# Sumo_Motor_Stepper_DC.net
KiCad netlist of a schematic drawn in Altium Designer
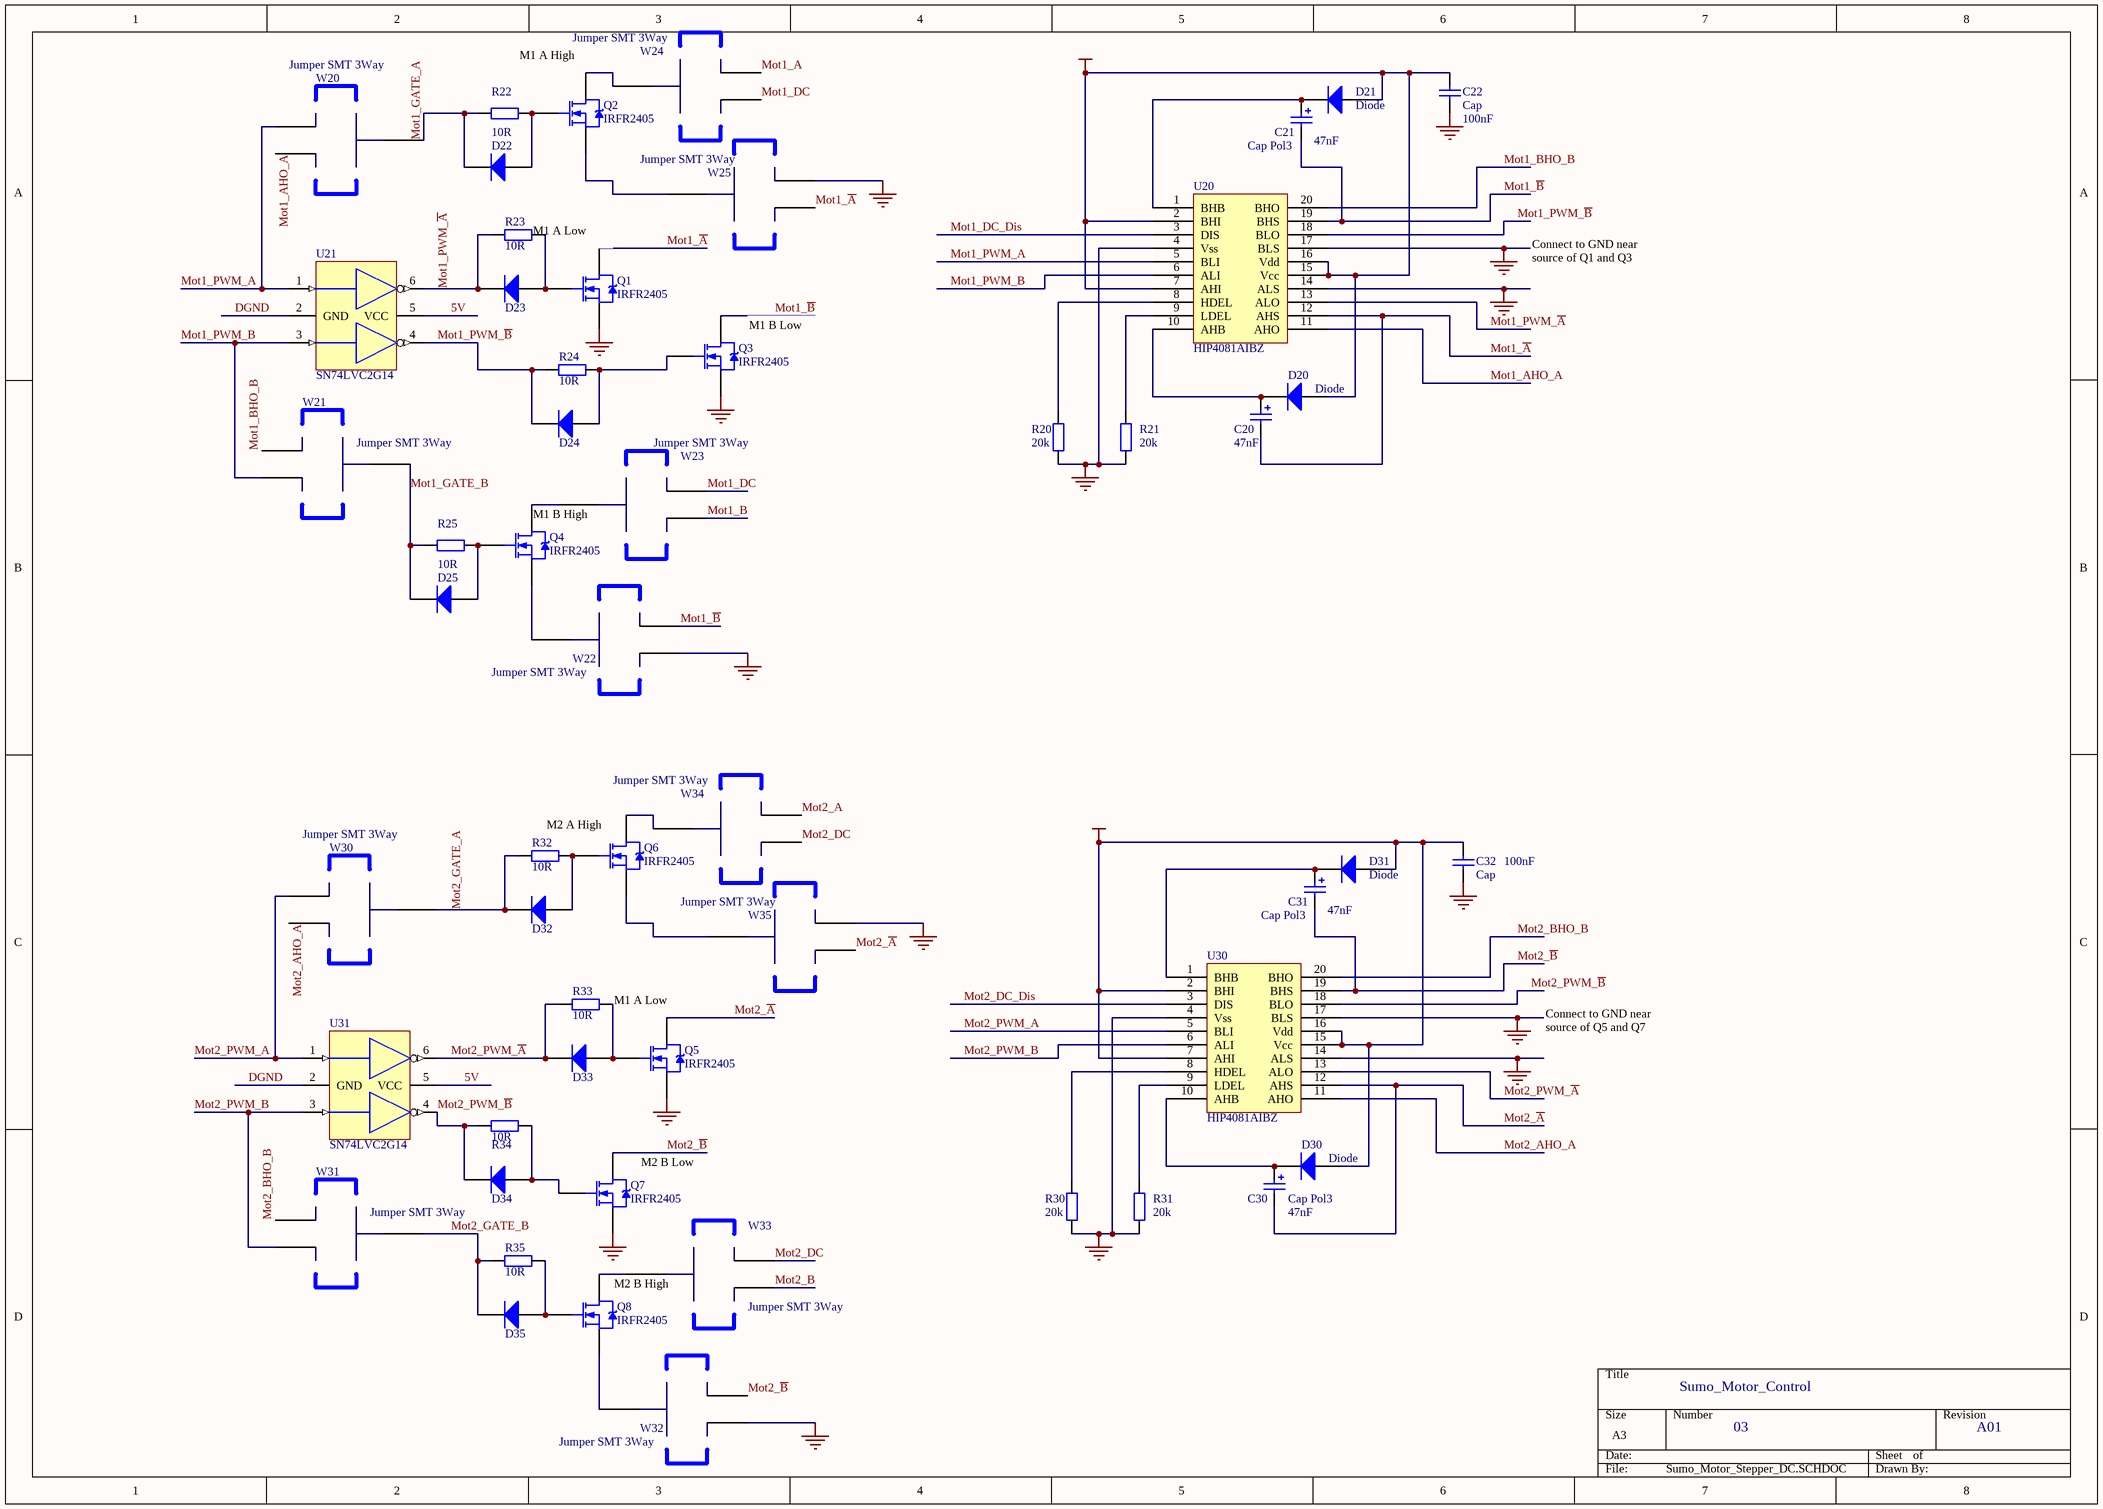
[diagram p0: Sumo_Motor_Stepper_DC.SCHDOC]

(export (version "E")
  (design (tool "Eeschema 10.0.6"))
  (components
    (comp (ref "C20")
      (value "47nF")
      (footprint "CC2012-0805")
      (description "Polarized Capacitor (Surface Mount)")
      (fields (field (name "Comment") "Cap Pol3") (field (name "PUBLISHER") "Altium Limited"))
      (libsource (lib "*") (part "Cap Pol3"))
    )
    (comp (ref "C21")
      (value "Cap Pol3")
      (footprint "CC2012-0805")
      (description "Polarized Capacitor (Surface Mount)")
      (fields (field (name "ALTIUM_VALUE") "47nF") (field (name "PUBLISHER") "Altium Limited"))
      (libsource (lib "*") (part "Cap Pol3"))
    )
    (comp (ref "C22")
      (value "Cap")
      (footprint "CC2012-0805")
      (description "Capacitor")
      (fields (field (name "ALTIUM_VALUE") "100nF") (field (name "PUBLISHER") "Altium Limited"))
      (libsource (lib "*") (part "Cap"))
    )
    (comp (ref "C30")
      (value "Cap Pol3")
      (footprint "CC2012-0805")
      (description "Polarized Capacitor (Surface Mount)")
      (fields (field (name "ALTIUM_VALUE") "47nF") (field (name "PUBLISHER") "Altium Limited"))
      (libsource (lib "*") (part "Cap Pol3"))
    )
    (comp (ref "C31")
      (value "Cap Pol3")
      (footprint "CC2012-0805")
      (description "Polarized Capacitor (Surface Mount)")
      (fields (field (name "ALTIUM_VALUE") "47nF") (field (name "PUBLISHER") "Altium Limited"))
      (libsource (lib "*") (part "Cap Pol3"))
    )
    (comp (ref "C32")
      (value "Cap")
      (footprint "CC2012-0805")
      (description "Capacitor")
      (fields (field (name "ALTIUM_VALUE") "100nF") (field (name "PUBLISHER") "Altium Limited"))
      (libsource (lib "*") (part "Cap"))
    )
    (comp (ref "D20")
      (value "Diode")
      (footprint "SMA")
      (description "Default Diode")
      (fields (field (name "PUBLISHER") "Altium Limited"))
      (libsource (lib "*") (part "Diode"))
    )
    (comp (ref "D21")
      (value "Diode")
      (footprint "SMA")
      (description "Default Diode")
      (fields (field (name "PUBLISHER") "Altium Limited"))
      (libsource (lib "*") (part "Diode"))
    )
    (comp (ref "D22")
      (value "Diode")
      (footprint "SMA")
      (description "Default Diode")
      (fields (field (name "PUBLISHER") "Altium Limited"))
      (libsource (lib "*") (part "Diode"))
    )
    (comp (ref "D23")
      (value "Diode")
      (footprint "SMA")
      (description "Default Diode")
      (fields (field (name "PUBLISHER") "Altium Limited"))
      (libsource (lib "*") (part "Diode"))
    )
    (comp (ref "D24")
      (value "Diode")
      (footprint "SMA")
      (description "Default Diode")
      (fields (field (name "PUBLISHER") "Altium Limited"))
      (libsource (lib "*") (part "Diode"))
    )
    (comp (ref "D25")
      (value "Diode")
      (footprint "SMA")
      (description "Default Diode")
      (fields (field (name "PUBLISHER") "Altium Limited"))
      (libsource (lib "*") (part "Diode"))
    )
    (comp (ref "D30")
      (value "Diode")
      (footprint "SMA")
      (description "Default Diode")
      (fields (field (name "PUBLISHER") "Altium Limited"))
      (libsource (lib "*") (part "Diode"))
    )
    (comp (ref "D31")
      (value "Diode")
      (footprint "SMA")
      (description "Default Diode")
      (fields (field (name "PUBLISHER") "Altium Limited"))
      (libsource (lib "*") (part "Diode"))
    )
    (comp (ref "D32")
      (value "Diode")
      (footprint "SMA")
      (description "Default Diode")
      (fields (field (name "PUBLISHER") "Altium Limited"))
      (libsource (lib "*") (part "Diode"))
    )
    (comp (ref "D33")
      (value "Diode")
      (footprint "SMA")
      (description "Default Diode")
      (fields (field (name "PUBLISHER") "Altium Limited"))
      (libsource (lib "*") (part "Diode"))
    )
    (comp (ref "D34")
      (value "Diode")
      (footprint "SMA")
      (description "Default Diode")
      (fields (field (name "PUBLISHER") "Altium Limited"))
      (libsource (lib "*") (part "Diode"))
    )
    (comp (ref "D35")
      (value "Diode")
      (footprint "SMA")
      (description "Default Diode")
      (fields (field (name "PUBLISHER") "Altium Limited"))
      (libsource (lib "*") (part "Diode"))
    )
    (comp (ref "Q1")
      (value "IRFR2405")
      (footprint "TO-252AA")
      (description "HEXFET Power MOSFET")
      (fields (field (name "PUBLISHER") "Altium Limited"))
      (libsource (lib "*") (part "IRFR2405"))
    )
    (comp (ref "Q2")
      (value "IRFR2405")
      (footprint "TO-252AA")
      (description "HEXFET Power MOSFET")
      (fields (field (name "PUBLISHER") "Altium Limited"))
      (libsource (lib "*") (part "IRFR2405"))
    )
    (comp (ref "Q3")
      (value "IRFR2405")
      (footprint "TO-252AA")
      (description "HEXFET Power MOSFET")
      (fields (field (name "PUBLISHER") "Altium Limited"))
      (libsource (lib "*") (part "IRFR2405"))
    )
    (comp (ref "Q4")
      (value "IRFR2405")
      (footprint "TO-252AA")
      (description "HEXFET Power MOSFET")
      (fields (field (name "PUBLISHER") "Altium Limited"))
      (libsource (lib "*") (part "IRFR2405"))
    )
    (comp (ref "Q5")
      (value "IRFR2405")
      (footprint "TO-252AA")
      (description "HEXFET Power MOSFET")
      (fields (field (name "PUBLISHER") "Altium Limited"))
      (libsource (lib "*") (part "IRFR2405"))
    )
    (comp (ref "Q6")
      (value "IRFR2405")
      (footprint "TO-252AA")
      (description "HEXFET Power MOSFET")
      (fields (field (name "PUBLISHER") "Altium Limited"))
      (libsource (lib "*") (part "IRFR2405"))
    )
    (comp (ref "Q7")
      (value "IRFR2405")
      (footprint "TO-252AA")
      (description "HEXFET Power MOSFET")
      (fields (field (name "PUBLISHER") "Altium Limited"))
      (libsource (lib "*") (part "IRFR2405"))
    )
    (comp (ref "Q8")
      (value "IRFR2405")
      (footprint "TO-252AA")
      (description "HEXFET Power MOSFET")
      (fields (field (name "PUBLISHER") "Altium Limited"))
      (libsource (lib "*") (part "IRFR2405"))
    )
    (comp (ref "R20")
      (value "20k")
      (footprint "CR2012-0805")
      (description "Semiconductor Resistor")
      (fields (field (name "Comment") "Res Semi") (field (name "PUBLISHER") "Altium Limited"))
      (libsource (lib "") (part "Res Semi_1"))
    )
    (comp (ref "R21")
      (value "20k")
      (footprint "CR2012-0805")
      (description "Semiconductor Resistor")
      (fields (field (name "Comment") "Res Semi") (field (name "PUBLISHER") "Altium Limited"))
      (libsource (lib "") (part "Res Semi_1"))
    )
    (comp (ref "R22")
      (value "10R")
      (footprint "CR2012-0805")
      (description "Semiconductor Resistor")
      (fields (field (name "Comment") "Res Semi") (field (name "PUBLISHER") "Altium Limited"))
      (libsource (lib "Miscellaneous Devices") (part "Res Semi"))
    )
    (comp (ref "R23")
      (value "10R")
      (footprint "CR2012-0805")
      (description "Semiconductor Resistor")
      (fields (field (name "Comment") "Res Semi") (field (name "PUBLISHER") "Altium Limited"))
      (libsource (lib "Miscellaneous Devices") (part "Res Semi"))
    )
    (comp (ref "R24")
      (value "10R")
      (footprint "CR2012-0805")
      (description "Semiconductor Resistor")
      (fields (field (name "Comment") "Res Semi") (field (name "PUBLISHER") "Altium Limited"))
      (libsource (lib "Miscellaneous Devices") (part "Res Semi"))
    )
    (comp (ref "R25")
      (value "10R")
      (footprint "CR2012-0805")
      (description "Semiconductor Resistor")
      (fields (field (name "Comment") "Res Semi") (field (name "PUBLISHER") "Altium Limited"))
      (libsource (lib "Miscellaneous Devices") (part "Res Semi"))
    )
    (comp (ref "R30")
      (value "20k")
      (footprint "CR2012-0805")
      (description "Semiconductor Resistor")
      (fields (field (name "Comment") "Res Semi") (field (name "PUBLISHER") "Altium Limited"))
      (libsource (lib "") (part "Res Semi_1"))
    )
    (comp (ref "R31")
      (value "20k")
      (footprint "CR2012-0805")
      (description "Semiconductor Resistor")
      (fields (field (name "Comment") "Res Semi") (field (name "PUBLISHER") "Altium Limited"))
      (libsource (lib "") (part "Res Semi_1"))
    )
    (comp (ref "R32")
      (value "10R")
      (footprint "CR2012-0805")
      (description "Semiconductor Resistor")
      (fields (field (name "Comment") "Res Semi") (field (name "PUBLISHER") "Altium Limited"))
      (libsource (lib "Miscellaneous Devices") (part "Res Semi"))
    )
    (comp (ref "R33")
      (value "10R")
      (footprint "CR2012-0805")
      (description "Semiconductor Resistor")
      (fields (field (name "Comment") "Res Semi") (field (name "PUBLISHER") "Altium Limited"))
      (libsource (lib "Miscellaneous Devices") (part "Res Semi"))
    )
    (comp (ref "R34")
      (value "10R")
      (footprint "CR2012-0805")
      (description "Semiconductor Resistor")
      (fields (field (name "Comment") "Res Semi") (field (name "PUBLISHER") "Altium Limited"))
      (libsource (lib "Miscellaneous Devices") (part "Res Semi"))
    )
    (comp (ref "R35")
      (value "10R")
      (footprint "CR2012-0805")
      (description "Semiconductor Resistor")
      (fields (field (name "Comment") "Res Semi") (field (name "PUBLISHER") "Altium Limited"))
      (libsource (lib "Miscellaneous Devices") (part "Res Semi"))
    )
    (comp (ref "U20")
      (value "HIP4081AIBZ")
      (footprint "SOIC20A")
      (description "80V/2.5A Peak, High Frequency Full Bridge FET Driver")
      (libsource (lib "*") (part "HIP4081AIBZ"))
    )
    (comp (ref "U21")
      (value "SN74LVC2G14")
      (footprint "SC70")
      (description "Dual Schmitt-Trigger Inverter")
      (fields (field (name "PUBLISHER") "Altium Limited"))
      (libsource (lib "*") (part "SN74LVC2G14"))
    )
    (comp (ref "U30")
      (value "HIP4081AIBZ")
      (footprint "SOIC20A")
      (description "80V/2.5A Peak, High Frequency Full Bridge FET Driver")
      (libsource (lib "*") (part "HIP4081AIBZ"))
    )
    (comp (ref "U31")
      (value "SN74LVC2G14")
      (footprint "SC70")
      (description "Dual Schmitt-Trigger Inverter")
      (fields (field (name "PUBLISHER") "Altium Limited"))
      (libsource (lib "*") (part "SN74LVC2G14"))
    )
    (comp (ref "W20")
      (value "Jumper SMT 3Way")
      (footprint "Jumper SMT 3 Way")
      (libsource (lib "*") (part "Jumper SMT 3Way"))
    )
    (comp (ref "W21")
      (value "Jumper SMT 3Way")
      (footprint "Jumper SMT 3 Way")
      (libsource (lib "*") (part "Jumper SMT 3Way"))
    )
    (comp (ref "W22")
      (value "Jumper SMT 3Way")
      (footprint "Jumper SMT 3 Way")
      (libsource (lib "*") (part "Jumper SMT 3Way"))
    )
    (comp (ref "W23")
      (value "Jumper SMT 3Way")
      (footprint "Jumper SMT 3 Way")
      (libsource (lib "*") (part "Jumper SMT 3Way"))
    )
    (comp (ref "W24")
      (value "Jumper SMT 3Way")
      (footprint "Jumper SMT 3 Way")
      (libsource (lib "*") (part "Jumper SMT 3Way"))
    )
    (comp (ref "W25")
      (value "Jumper SMT 3Way")
      (footprint "Jumper SMT 3 Way")
      (libsource (lib "*") (part "Jumper SMT 3Way"))
    )
    (comp (ref "W30")
      (value "Jumper SMT 3Way")
      (footprint "Jumper SMT 3 Way")
      (libsource (lib "*") (part "Jumper SMT 3Way"))
    )
    (comp (ref "W31")
      (value "Jumper SMT 3Way")
      (footprint "Jumper SMT 3 Way")
      (libsource (lib "*") (part "Jumper SMT 3Way"))
    )
    (comp (ref "W32")
      (value "Jumper SMT 3Way")
      (footprint "Jumper SMT 3 Way")
      (libsource (lib "*") (part "Jumper SMT 3Way"))
    )
    (comp (ref "W33")
      (value "Jumper SMT 3Way")
      (footprint "Jumper SMT 3 Way")
      (libsource (lib "*") (part "Jumper SMT 3Way"))
    )
    (comp (ref "W34")
      (value "Jumper SMT 3Way")
      (footprint "Jumper SMT 3 Way")
      (libsource (lib "*") (part "Jumper SMT 3Way"))
    )
    (comp (ref "W35")
      (value "Jumper SMT 3Way")
      (footprint "Jumper SMT 3 Way")
      (libsource (lib "*") (part "Jumper SMT 3Way"))
    )
  )
  (nets
    (net (code "1") (name "/5V") (class "Default")
      (node (ref "U21") (pin "5") (pinfunction "VCC_5") (pintype "power_in"))
      (node (ref "U31") (pin "5") (pinfunction "VCC_5") (pintype "power_in"))
    )
    (net (code "2") (name "/Mot1_A") (class "Default")
      (node (ref "W24") (pin "2") (pinfunction "Out1_2") (pintype "passive"))
    )
    (net (code "3") (name "/Mot1_AHO_A") (class "Default")
      (node (ref "U20") (pin "11") (pinfunction "AHO_11") (pintype "passive"))
      (node (ref "W20") (pin "2") (pinfunction "Out1_2") (pintype "passive"))
    )
    (net (code "4") (name "/Mot1_B") (class "Default")
      (node (ref "W23") (pin "3") (pinfunction "Out2_3") (pintype "passive"))
    )
    (net (code "5") (name "/Mot1_BHO_B") (class "Default")
      (node (ref "U20") (pin "20") (pinfunction "BHO_20") (pintype "passive"))
      (node (ref "W21") (pin "3") (pinfunction "Out2_3") (pintype "passive"))
    )
    (net (code "6") (name "/Mot1_DC") (class "Default")
      (node (ref "W23") (pin "2") (pinfunction "Out1_2") (pintype "passive"))
      (node (ref "W24") (pin "3") (pinfunction "Out2_3") (pintype "passive"))
    )
    (net (code "7") (name "/Mot1_DC_Dis") (class "Default")
      (node (ref "U20") (pin "3") (pinfunction "DIS_3") (pintype "passive"))
    )
    (net (code "8") (name "/Mot1_GATE_A") (class "Default")
      (node (ref "D22") (pin "2") (pinfunction "K_2") (pintype "passive"))
      (node (ref "R22") (pin "1") (pinfunction "1_1") (pintype "passive"))
      (node (ref "W20") (pin "1") (pinfunction "In_1") (pintype "passive"))
    )
    (net (code "9") (name "/Mot1_GATE_B") (class "Default")
      (node (ref "D25") (pin "2") (pinfunction "K_2") (pintype "passive"))
      (node (ref "R25") (pin "1") (pinfunction "1_1") (pintype "passive"))
      (node (ref "W21") (pin "1") (pinfunction "In_1") (pintype "passive"))
    )
    (net (code "10") (name "/Mot1_PWM_A") (class "Default")
      (node (ref "U20") (pin "5") (pinfunction "BLI_5") (pintype "passive"))
      (node (ref "U21") (pin "1") (pinfunction "A_1") (pintype "input"))
      (node (ref "W20") (pin "3") (pinfunction "Out2_3") (pintype "passive"))
    )
    (net (code "11") (name "/Mot1_PWM_B") (class "Default")
      (node (ref "U20") (pin "6") (pinfunction "ALI_6") (pintype "passive"))
      (node (ref "U21") (pin "3") (pinfunction "A_3") (pintype "input"))
      (node (ref "W21") (pin "2") (pinfunction "Out1_2") (pintype "passive"))
    )
    (net (code "12") (name "/Mot1_PWM_~{A}") (class "Default")
      (node (ref "D23") (pin "2") (pinfunction "K_2") (pintype "passive"))
      (node (ref "R23") (pin "1") (pinfunction "1_1") (pintype "passive"))
      (node (ref "U20") (pin "13") (pinfunction "ALO_13") (pintype "passive"))
      (node (ref "U21") (pin "6") (pinfunction "Y_6") (pintype "output"))
    )
    (net (code "13") (name "/Mot1_PWM_~{B}") (class "Default")
      (node (ref "D24") (pin "2") (pinfunction "K_2") (pintype "passive"))
      (node (ref "R24") (pin "1") (pinfunction "1_1") (pintype "passive"))
      (node (ref "U20") (pin "18") (pinfunction "BLO_18") (pintype "passive"))
      (node (ref "U21") (pin "4") (pinfunction "Y_4") (pintype "output"))
    )
    (net (code "14") (name "/Mot1_~{A}") (class "Default")
      (node (ref "C20") (pin "2") (pinfunction "2_2") (pintype "passive"))
      (node (ref "Q1") (pin "4") (pinfunction "D_4") (pintype "passive"))
      (node (ref "U20") (pin "12") (pinfunction "AHS_12") (pintype "passive"))
      (node (ref "W25") (pin "3") (pinfunction "Out2_3") (pintype "passive"))
    )
    (net (code "15") (name "/Mot1_~{B}") (class "Default")
      (node (ref "C21") (pin "2") (pinfunction "2_2") (pintype "passive"))
      (node (ref "Q3") (pin "4") (pinfunction "D_4") (pintype "passive"))
      (node (ref "U20") (pin "19") (pinfunction "BHS_19") (pintype "passive"))
      (node (ref "W22") (pin "2") (pinfunction "Out1_2") (pintype "passive"))
    )
    (net (code "16") (name "/Mot2_A") (class "Default")
      (node (ref "W34") (pin "2") (pinfunction "Out1_2") (pintype "passive"))
    )
    (net (code "17") (name "/Mot2_AHO_A") (class "Default")
      (node (ref "U30") (pin "11") (pinfunction "AHO_11") (pintype "passive"))
      (node (ref "W30") (pin "2") (pinfunction "Out1_2") (pintype "passive"))
    )
    (net (code "18") (name "/Mot2_B") (class "Default")
      (node (ref "W33") (pin "3") (pinfunction "Out2_3") (pintype "passive"))
    )
    (net (code "19") (name "/Mot2_BHO_B") (class "Default")
      (node (ref "U30") (pin "20") (pinfunction "BHO_20") (pintype "passive"))
      (node (ref "W31") (pin "3") (pinfunction "Out2_3") (pintype "passive"))
    )
    (net (code "20") (name "/Mot2_DC") (class "Default")
      (node (ref "W33") (pin "2") (pinfunction "Out1_2") (pintype "passive"))
      (node (ref "W34") (pin "3") (pinfunction "Out2_3") (pintype "passive"))
    )
    (net (code "21") (name "/Mot2_DC_Dis") (class "Default")
      (node (ref "U30") (pin "3") (pinfunction "DIS_3") (pintype "passive"))
    )
    (net (code "22") (name "/Mot2_GATE_A") (class "Default")
      (node (ref "D32") (pin "2") (pinfunction "K_2") (pintype "passive"))
      (node (ref "R32") (pin "1") (pinfunction "1_1") (pintype "passive"))
      (node (ref "W30") (pin "1") (pinfunction "In_1") (pintype "passive"))
    )
    (net (code "23") (name "/Mot2_GATE_B") (class "Default")
      (node (ref "D35") (pin "2") (pinfunction "K_2") (pintype "passive"))
      (node (ref "R35") (pin "1") (pinfunction "1_1") (pintype "passive"))
      (node (ref "W31") (pin "1") (pinfunction "In_1") (pintype "passive"))
    )
    (net (code "24") (name "/Mot2_PWM_A") (class "Default")
      (node (ref "U30") (pin "5") (pinfunction "BLI_5") (pintype "passive"))
      (node (ref "U31") (pin "1") (pinfunction "A_1") (pintype "input"))
      (node (ref "W30") (pin "3") (pinfunction "Out2_3") (pintype "passive"))
    )
    (net (code "25") (name "/Mot2_PWM_B") (class "Default")
      (node (ref "U30") (pin "6") (pinfunction "ALI_6") (pintype "passive"))
      (node (ref "U31") (pin "3") (pinfunction "A_3") (pintype "input"))
      (node (ref "W31") (pin "2") (pinfunction "Out1_2") (pintype "passive"))
    )
    (net (code "26") (name "/Mot2_PWM_~{A}") (class "Default")
      (node (ref "D33") (pin "2") (pinfunction "K_2") (pintype "passive"))
      (node (ref "R33") (pin "1") (pinfunction "1_1") (pintype "passive"))
      (node (ref "U30") (pin "13") (pinfunction "ALO_13") (pintype "passive"))
      (node (ref "U31") (pin "6") (pinfunction "Y_6") (pintype "output"))
    )
    (net (code "27") (name "/Mot2_PWM_~{B}") (class "Default")
      (node (ref "D34") (pin "2") (pinfunction "K_2") (pintype "passive"))
      (node (ref "R34") (pin "1") (pinfunction "1_1") (pintype "passive"))
      (node (ref "U30") (pin "18") (pinfunction "BLO_18") (pintype "passive"))
      (node (ref "U31") (pin "4") (pinfunction "Y_4") (pintype "output"))
    )
    (net (code "28") (name "/Mot2_~{A}") (class "Default")
      (node (ref "C30") (pin "2") (pinfunction "2_2") (pintype "passive"))
      (node (ref "Q5") (pin "4") (pinfunction "D_4") (pintype "passive"))
      (node (ref "U30") (pin "12") (pinfunction "AHS_12") (pintype "passive"))
      (node (ref "W35") (pin "3") (pinfunction "Out2_3") (pintype "passive"))
    )
    (net (code "29") (name "/Mot2_~{B}") (class "Default")
      (node (ref "C31") (pin "2") (pinfunction "2_2") (pintype "passive"))
      (node (ref "Q7") (pin "4") (pinfunction "D_4") (pintype "passive"))
      (node (ref "U30") (pin "19") (pinfunction "BHS_19") (pintype "passive"))
      (node (ref "W32") (pin "2") (pinfunction "Out1_2") (pintype "passive"))
    )
    (net (code "30") (name "12V") (class "Default")
      (node (ref "C22") (pin "2") (pinfunction "2_2") (pintype "passive"))
      (node (ref "C32") (pin "2") (pinfunction "2_2") (pintype "passive"))
      (node (ref "D20") (pin "1") (pinfunction "A_1") (pintype "passive"))
      (node (ref "D21") (pin "1") (pinfunction "A_1") (pintype "passive"))
      (node (ref "D30") (pin "1") (pinfunction "A_1") (pintype "passive"))
      (node (ref "D31") (pin "1") (pinfunction "A_1") (pintype "passive"))
      (node (ref "U20") (pin "15") (pinfunction "Vcc_15") (pintype "passive"))
      (node (ref "U20") (pin "16") (pinfunction "Vdd_16") (pintype "passive"))
      (node (ref "U20") (pin "2") (pinfunction "BHI_2") (pintype "passive"))
      (node (ref "U20") (pin "7") (pinfunction "AHI_7") (pintype "passive"))
      (node (ref "U30") (pin "15") (pinfunction "Vcc_15") (pintype "passive"))
      (node (ref "U30") (pin "16") (pinfunction "Vdd_16") (pintype "passive"))
      (node (ref "U30") (pin "2") (pinfunction "BHI_2") (pintype "passive"))
      (node (ref "U30") (pin "7") (pinfunction "AHI_7") (pintype "passive"))
    )
    (net (code "31") (name "DGND") (class "Default")
      (node (ref "C22") (pin "1") (pinfunction "1_1") (pintype "passive"))
      (node (ref "C32") (pin "1") (pinfunction "1_1") (pintype "passive"))
      (node (ref "R20") (pin "1") (pinfunction "1_1") (pintype "passive"))
      (node (ref "R21") (pin "1") (pinfunction "1_1") (pintype "passive"))
      (node (ref "R30") (pin "1") (pinfunction "1_1") (pintype "passive"))
      (node (ref "R31") (pin "1") (pinfunction "1_1") (pintype "passive"))
      (node (ref "U20") (pin "4") (pinfunction "Vss_4") (pintype "passive"))
      (node (ref "U21") (pin "2") (pinfunction "GND_2") (pintype "power_in"))
      (node (ref "U30") (pin "4") (pinfunction "Vss_4") (pintype "passive"))
      (node (ref "U31") (pin "2") (pinfunction "GND_2") (pintype "power_in"))
    )
    (net (code "32") (name "GND") (class "Default")
      (node (ref "Q1") (pin "3") (pinfunction "S_3") (pintype "passive"))
      (node (ref "Q3") (pin "3") (pinfunction "S_3") (pintype "passive"))
      (node (ref "Q5") (pin "3") (pinfunction "S_3") (pintype "passive"))
      (node (ref "Q7") (pin "3") (pinfunction "S_3") (pintype "passive"))
      (node (ref "U20") (pin "14") (pinfunction "ALS_14") (pintype "passive"))
      (node (ref "U20") (pin "17") (pinfunction "BLS_17") (pintype "passive"))
      (node (ref "U30") (pin "14") (pinfunction "ALS_14") (pintype "passive"))
      (node (ref "U30") (pin "17") (pinfunction "BLS_17") (pintype "passive"))
      (node (ref "W22") (pin "3") (pinfunction "Out2_3") (pintype "passive"))
      (node (ref "W25") (pin "2") (pinfunction "Out1_2") (pintype "passive"))
      (node (ref "W32") (pin "3") (pinfunction "Out2_3") (pintype "passive"))
      (node (ref "W35") (pin "2") (pinfunction "Out1_2") (pintype "passive"))
    )
    (net (code "33") (name "Net-(D20-K)") (class "Default")
      (node (ref "C20") (pin "1") (pinfunction "1_1") (pintype "passive"))
      (node (ref "D20") (pin "2") (pinfunction "K_2") (pintype "passive"))
      (node (ref "U20") (pin "10") (pinfunction "AHB_10") (pintype "passive"))
    )
    (net (code "34") (name "Net-(D21-K)") (class "Default")
      (node (ref "C21") (pin "1") (pinfunction "1_1") (pintype "passive"))
      (node (ref "D21") (pin "2") (pinfunction "K_2") (pintype "passive"))
      (node (ref "U20") (pin "1") (pinfunction "BHB_1") (pintype "passive"))
    )
    (net (code "35") (name "Net-(D22-A)") (class "Default")
      (node (ref "D22") (pin "1") (pinfunction "A_1") (pintype "passive"))
      (node (ref "Q2") (pin "1") (pinfunction "G_1") (pintype "passive"))
      (node (ref "R22") (pin "2") (pinfunction "2_2") (pintype "passive"))
    )
    (net (code "36") (name "Net-(D23-A)") (class "Default")
      (node (ref "D23") (pin "1") (pinfunction "A_1") (pintype "passive"))
      (node (ref "Q1") (pin "1") (pinfunction "G_1") (pintype "passive"))
      (node (ref "R23") (pin "2") (pinfunction "2_2") (pintype "passive"))
    )
    (net (code "37") (name "Net-(D24-A)") (class "Default")
      (node (ref "D24") (pin "1") (pinfunction "A_1") (pintype "passive"))
      (node (ref "Q3") (pin "1") (pinfunction "G_1") (pintype "passive"))
      (node (ref "R24") (pin "2") (pinfunction "2_2") (pintype "passive"))
    )
    (net (code "38") (name "Net-(D25-A)") (class "Default")
      (node (ref "D25") (pin "1") (pinfunction "A_1") (pintype "passive"))
      (node (ref "Q4") (pin "1") (pinfunction "G_1") (pintype "passive"))
      (node (ref "R25") (pin "2") (pinfunction "2_2") (pintype "passive"))
    )
    (net (code "39") (name "Net-(D30-K)") (class "Default")
      (node (ref "C30") (pin "1") (pinfunction "1_1") (pintype "passive"))
      (node (ref "D30") (pin "2") (pinfunction "K_2") (pintype "passive"))
      (node (ref "U30") (pin "10") (pinfunction "AHB_10") (pintype "passive"))
    )
    (net (code "40") (name "Net-(D31-K)") (class "Default")
      (node (ref "C31") (pin "1") (pinfunction "1_1") (pintype "passive"))
      (node (ref "D31") (pin "2") (pinfunction "K_2") (pintype "passive"))
      (node (ref "U30") (pin "1") (pinfunction "BHB_1") (pintype "passive"))
    )
    (net (code "41") (name "Net-(D32-A)") (class "Default")
      (node (ref "D32") (pin "1") (pinfunction "A_1") (pintype "passive"))
      (node (ref "Q6") (pin "1") (pinfunction "G_1") (pintype "passive"))
      (node (ref "R32") (pin "2") (pinfunction "2_2") (pintype "passive"))
    )
    (net (code "42") (name "Net-(D33-A)") (class "Default")
      (node (ref "D33") (pin "1") (pinfunction "A_1") (pintype "passive"))
      (node (ref "Q5") (pin "1") (pinfunction "G_1") (pintype "passive"))
      (node (ref "R33") (pin "2") (pinfunction "2_2") (pintype "passive"))
    )
    (net (code "43") (name "Net-(D34-A)") (class "Default")
      (node (ref "D34") (pin "1") (pinfunction "A_1") (pintype "passive"))
      (node (ref "Q7") (pin "1") (pinfunction "G_1") (pintype "passive"))
      (node (ref "R34") (pin "2") (pinfunction "2_2") (pintype "passive"))
    )
    (net (code "44") (name "Net-(D35-A)") (class "Default")
      (node (ref "D35") (pin "1") (pinfunction "A_1") (pintype "passive"))
      (node (ref "Q8") (pin "1") (pinfunction "G_1") (pintype "passive"))
      (node (ref "R35") (pin "2") (pinfunction "2_2") (pintype "passive"))
    )
    (net (code "45") (name "Net-(Q2-D)") (class "Default")
      (node (ref "Q2") (pin "4") (pinfunction "D_4") (pintype "passive"))
      (node (ref "W24") (pin "1") (pinfunction "In_1") (pintype "passive"))
    )
    (net (code "46") (name "Net-(Q2-S)") (class "Default")
      (node (ref "Q2") (pin "3") (pinfunction "S_3") (pintype "passive"))
      (node (ref "W25") (pin "1") (pinfunction "In_1") (pintype "passive"))
    )
    (net (code "47") (name "Net-(Q4-D)") (class "Default")
      (node (ref "Q4") (pin "4") (pinfunction "D_4") (pintype "passive"))
      (node (ref "W23") (pin "1") (pinfunction "In_1") (pintype "passive"))
    )
    (net (code "48") (name "Net-(Q4-S)") (class "Default")
      (node (ref "Q4") (pin "3") (pinfunction "S_3") (pintype "passive"))
      (node (ref "W22") (pin "1") (pinfunction "In_1") (pintype "passive"))
    )
    (net (code "49") (name "Net-(Q6-D)") (class "Default")
      (node (ref "Q6") (pin "4") (pinfunction "D_4") (pintype "passive"))
      (node (ref "W34") (pin "1") (pinfunction "In_1") (pintype "passive"))
    )
    (net (code "50") (name "Net-(Q6-S)") (class "Default")
      (node (ref "Q6") (pin "3") (pinfunction "S_3") (pintype "passive"))
      (node (ref "W35") (pin "1") (pinfunction "In_1") (pintype "passive"))
    )
    (net (code "51") (name "Net-(Q8-D)") (class "Default")
      (node (ref "Q8") (pin "4") (pinfunction "D_4") (pintype "passive"))
      (node (ref "W33") (pin "1") (pinfunction "In_1") (pintype "passive"))
    )
    (net (code "52") (name "Net-(Q8-S)") (class "Default")
      (node (ref "Q8") (pin "3") (pinfunction "S_3") (pintype "passive"))
      (node (ref "W32") (pin "1") (pinfunction "In_1") (pintype "passive"))
    )
    (net (code "53") (name "Net-(U20-HDEL)") (class "Default")
      (node (ref "R20") (pin "2") (pinfunction "2_2") (pintype "passive"))
      (node (ref "U20") (pin "8") (pinfunction "HDEL_8") (pintype "passive"))
    )
    (net (code "54") (name "Net-(U20-LDEL)") (class "Default")
      (node (ref "R21") (pin "2") (pinfunction "2_2") (pintype "passive"))
      (node (ref "U20") (pin "9") (pinfunction "LDEL_9") (pintype "passive"))
    )
    (net (code "55") (name "Net-(U30-HDEL)") (class "Default")
      (node (ref "R30") (pin "2") (pinfunction "2_2") (pintype "passive"))
      (node (ref "U30") (pin "8") (pinfunction "HDEL_8") (pintype "passive"))
    )
    (net (code "56") (name "Net-(U30-LDEL)") (class "Default")
      (node (ref "R31") (pin "2") (pinfunction "2_2") (pintype "passive"))
      (node (ref "U30") (pin "9") (pinfunction "LDEL_9") (pintype "passive"))
    )
  )
)
